# DST800_NMEA2k-CAN_Indicator.net
KiCad netlist of a schematic drawn in Altium Designer
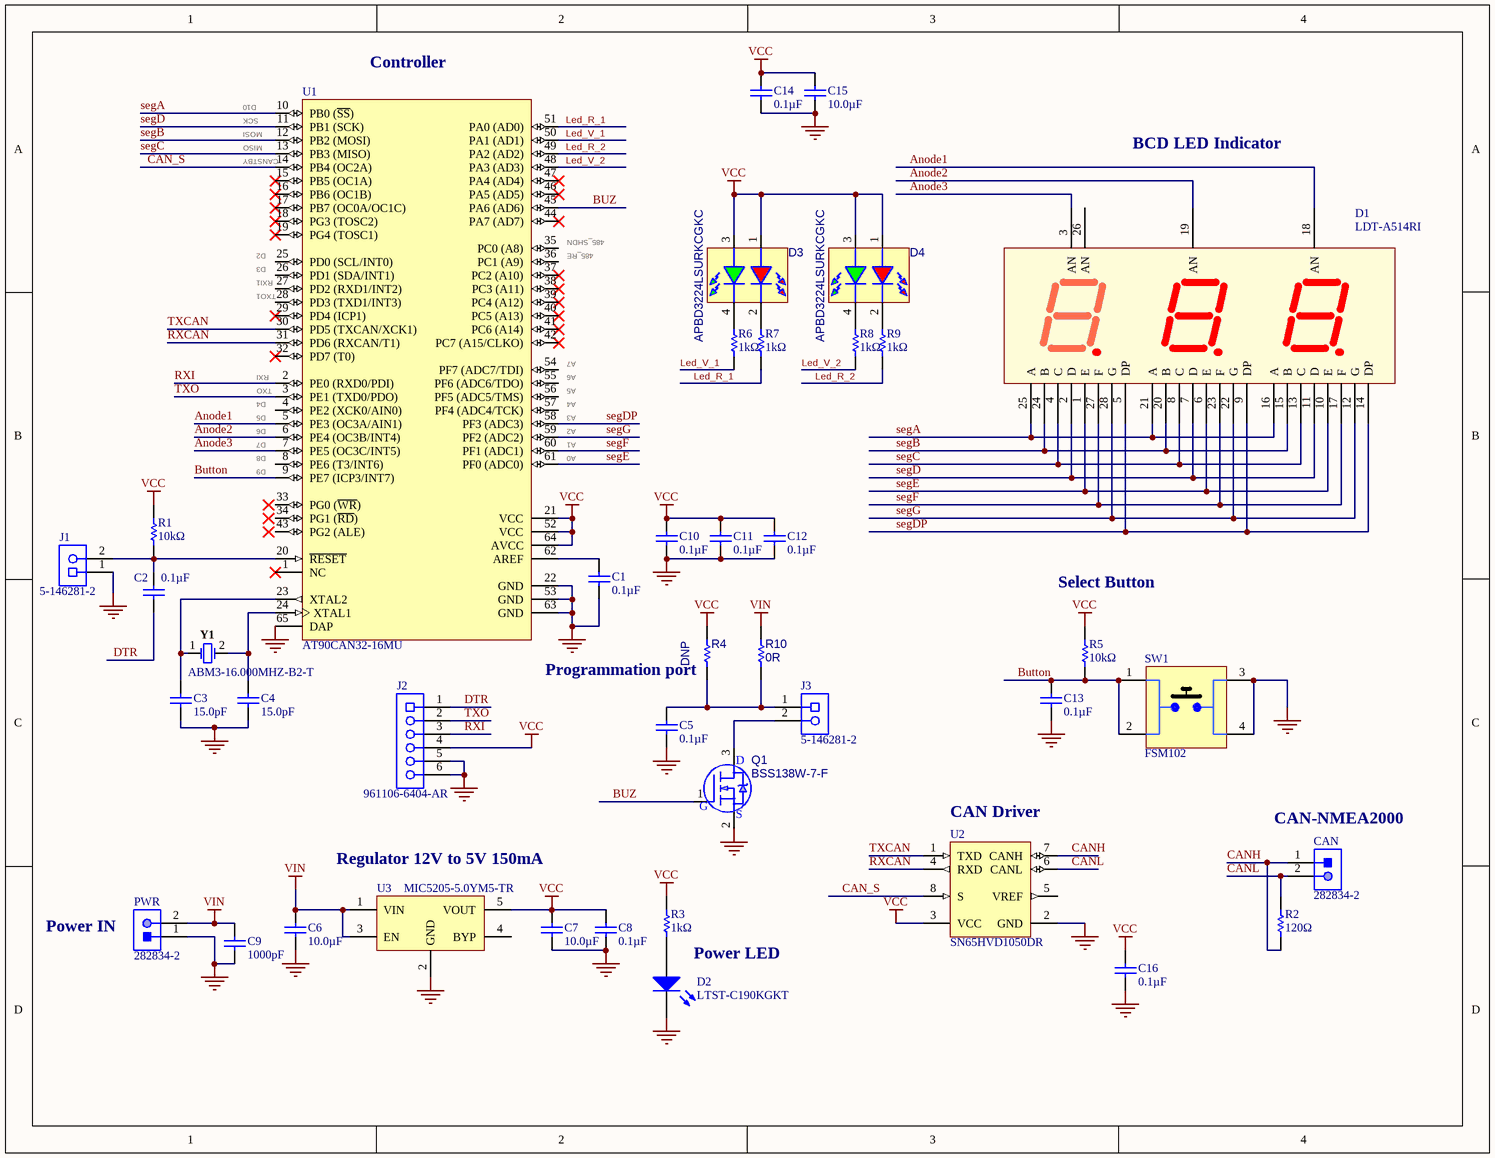
[diagram p0: DST800_NMEA2k-CAN_Indicator.SchDoc]

(export (version "E")
  (design (tool "Eeschema 10.0.6"))
  (components
    (comp (ref "C1")
      (value "0.1µF")
      (footprint "PCB-mhhqftc5ilnrg4qi8ds6-1")
      (description "CAP CER 0.1uF 50V X7R 0603")
      (fields
        (field (name "MANUFACTURER") "Samsung Electro-Mechanics")
        (field (name "MANUFACTURERPARTNUMBER") "CL10B104KB8NNNC")
      )
      (libsource (lib "DST800_NMEA2k-CAN_Indicator") (part "CMP-1af8d38ac64bc53f-5"))
    )
    (comp (ref "C2")
      (value "0.1µF")
      (footprint "PCB-mhhqftc5ilnrg4qi8ds6-1")
      (description "CAP CER 0.1uF 50V X7R 0603")
      (fields
        (field (name "MANUFACTURER") "Samsung Electro-Mechanics")
        (field (name "MANUFACTURERPARTNUMBER") "CL10B104KB8NNNC")
      )
      (libsource (lib "DST800_NMEA2k-CAN_Indicator") (part "CMP-1af8d38ac64bc53f-5"))
    )
    (comp (ref "C3")
      (value "15.0pF")
      (footprint "PCB-69ec8bfnjhyebnpbrrfx-1")
      (description "CAP CER 15pF ±5% 50V C0G/NP0 0603 [1608]")
      (fields
        (field (name "MANUFACTURER") "TDK")
        (field (name "MANUFACTURERPARTNUMBER") "C1608C0G1H150J080AA")
      )
      (libsource (lib "DST800_NMEA2k-CAN_Indicator") (part "CMP-57259fa49f8088e2-2"))
    )
    (comp (ref "C4")
      (value "15.0pF")
      (footprint "PCB-69ec8bfnjhyebnpbrrfx-1")
      (description "CAP CER 15pF ±5% 50V C0G/NP0 0603 [1608]")
      (fields
        (field (name "MANUFACTURER") "TDK")
        (field (name "MANUFACTURERPARTNUMBER") "C1608C0G1H150J080AA")
      )
      (libsource (lib "DST800_NMEA2k-CAN_Indicator") (part "CMP-57259fa49f8088e2-2"))
    )
    (comp (ref "C5")
      (value "0.1µF")
      (footprint "PCB-mhhqftc5ilnrg4qi8ds6-1")
      (description "CAP CER 0.1uF 50V X7R 0603")
      (fields
        (field (name "MANUFACTURER") "Samsung Electro-Mechanics")
        (field (name "MANUFACTURERPARTNUMBER") "CL10B104KB8NNNC")
      )
      (libsource (lib "DST800_NMEA2k-CAN_Indicator") (part "CMP-1af8d38ac64bc53f-5"))
    )
    (comp (ref "C6")
      (value "10.0µF")
      (footprint "PCB-j0jk5xr8qbnaskonccg4-1")
      (description "CAP CER 10uF ±10% 25V X7R 1210")
      (fields
        (field (name "MANUFACTURER") "TDK")
        (field (name "MANUFACTURERPARTNUMBER") "C3225X7R1E106K250AC")
      )
      (libsource (lib "DST800_NMEA2k-CAN_Indicator") (part "CMP-2bdce35de069f41b-1"))
    )
    (comp (ref "C7")
      (value "10.0µF")
      (footprint "PCB-j0jk5xr8qbnaskonccg4-1")
      (description "CAP CER 10uF ±10% 25V X7R 1210")
      (fields
        (field (name "MANUFACTURER") "TDK")
        (field (name "MANUFACTURERPARTNUMBER") "C3225X7R1E106K250AC")
      )
      (libsource (lib "DST800_NMEA2k-CAN_Indicator") (part "CMP-2bdce35de069f41b-1"))
    )
    (comp (ref "C8")
      (value "0.1µF")
      (footprint "PCB-mhhqftc5ilnrg4qi8ds6-1")
      (description "CAP CER 0.1uF 50V X7R 0603")
      (fields
        (field (name "MANUFACTURER") "Samsung Electro-Mechanics")
        (field (name "MANUFACTURERPARTNUMBER") "CL10B104KB8NNNC")
      )
      (libsource (lib "DST800_NMEA2k-CAN_Indicator") (part "CMP-1af8d38ac64bc53f-5"))
    )
    (comp (ref "C9")
      (value "1000pF")
      (footprint "CAPC1608X90X35LL15T15")
      (description "CAP CER 1000pF ±20% 100V X7R 0603")
      (fields (field (name "MANUFACTURERPARTNUMBER") "06031C102MAT2A") (field (name "MANUFACTURER") "AVX"))
      (libsource (lib "DST800_NMEA2k-CAN_Indicator") (part "CMP-126202-2"))
    )
    (comp (ref "C10")
      (value "0.1µF")
      (footprint "PCB-mhhqftc5ilnrg4qi8ds6-1")
      (description "CAP CER 0.1uF 50V X7R 0603")
      (fields
        (field (name "MANUFACTURER") "Samsung Electro-Mechanics")
        (field (name "MANUFACTURERPARTNUMBER") "CL10B104KB8NNNC")
      )
      (libsource (lib "DST800_NMEA2k-CAN_Indicator") (part "CMP-1af8d38ac64bc53f-5"))
    )
    (comp (ref "C11")
      (value "0.1µF")
      (footprint "PCB-mhhqftc5ilnrg4qi8ds6-1")
      (description "CAP CER 0.1uF 50V X7R 0603")
      (fields
        (field (name "MANUFACTURER") "Samsung Electro-Mechanics")
        (field (name "MANUFACTURERPARTNUMBER") "CL10B104KB8NNNC")
      )
      (libsource (lib "DST800_NMEA2k-CAN_Indicator") (part "CMP-1af8d38ac64bc53f-5"))
    )
    (comp (ref "C12")
      (value "0.1µF")
      (footprint "PCB-mhhqftc5ilnrg4qi8ds6-1")
      (description "CAP CER 0.1uF 50V X7R 0603")
      (fields
        (field (name "MANUFACTURER") "Samsung Electro-Mechanics")
        (field (name "MANUFACTURERPARTNUMBER") "CL10B104KB8NNNC")
      )
      (libsource (lib "DST800_NMEA2k-CAN_Indicator") (part "CMP-1af8d38ac64bc53f-5"))
    )
    (comp (ref "C13")
      (value "0.1µF")
      (footprint "PCB-mhhqftc5ilnrg4qi8ds6-1")
      (description "CAP CER 0.1uF 50V X7R 0603")
      (fields
        (field (name "MANUFACTURER") "Samsung Electro-Mechanics")
        (field (name "MANUFACTURERPARTNUMBER") "CL10B104KB8NNNC")
      )
      (libsource (lib "DST800_NMEA2k-CAN_Indicator") (part "CMP-1af8d38ac64bc53f-5"))
    )
    (comp (ref "C14")
      (value "0.1µF")
      (footprint "PCB-mhhqftc5ilnrg4qi8ds6-1")
      (description "CAP CER 0.1uF 50V X7R 0603")
      (fields
        (field (name "MANUFACTURER") "Samsung Electro-Mechanics")
        (field (name "MANUFACTURERPARTNUMBER") "CL10B104KB8NNNC")
      )
      (libsource (lib "DST800_NMEA2k-CAN_Indicator") (part "CMP-1af8d38ac64bc53f-5"))
    )
    (comp (ref "C15")
      (value "10.0µF")
      (footprint "PCB-j0jk5xr8qbnaskonccg4-1")
      (description "CAP CER 10uF ±10% 25V X7R 1210")
      (fields
        (field (name "MANUFACTURER") "TDK")
        (field (name "MANUFACTURERPARTNUMBER") "C3225X7R1E106K250AC")
      )
      (libsource (lib "DST800_NMEA2k-CAN_Indicator") (part "CMP-2bdce35de069f41b-1"))
    )
    (comp (ref "C16")
      (value "0.1µF")
      (footprint "PCB-mhhqftc5ilnrg4qi8ds6-1")
      (description "CAP CER 0.1uF 50V X7R 0603")
      (fields
        (field (name "MANUFACTURER") "Samsung Electro-Mechanics")
        (field (name "MANUFACTURERPARTNUMBER") "CL10B104KB8NNNC")
      )
      (libsource (lib "DST800_NMEA2k-CAN_Indicator") (part "CMP-1af8d38ac64bc53f-5"))
    )
    (comp (ref "CAN")
      (value "282834-2")
      (footprint "PCB-0kdx5sneyudsmu18l6zv-1")
      (description "CONN Terminal Block; 16-30 AWG 0.197 in")
      (fields (field (name "MANUFACTURER") "TE Connectivity"))
      (libsource (lib "DST800_NMEA2k-CAN_Indicator") (part "CMP-369bfdc835bbe95c-32"))
    )
    (comp (ref "D1")
      (value "LDT-A514RI")
      (footprint "LDTA514RI")
      (description "Display 3-digit 7-Seg 0.56 in")
      (fields (field (name "MANUFACTURER") "Lumex"))
      (libsource (lib "DST800_NMEA2k-CAN_Indicator") (part "CMP-6dbba4b18441b27c-1"))
    )
    (comp (ref "D2")
      (value "LTST-C190KGKT")
      (footprint "PCB-eapfwhp0rnksgujf96h3-1")
      (description "LED 0603 green")
      (fields (field (name "MANUFACTURER") "Lite-On"))
      (libsource (lib "DST800_NMEA2k-CAN_Indicator") (part "CMP-e1642866a00b3ea3-3"))
    )
    (comp (ref "D3")
      (value "APBD3224LSURKCGKC")
      (footprint "DS_LED_3224")
      (description "LED Red and Yellow-Green")
      (fields (field (name "MANUFACTURER") "Kingbright"))
      (libsource (lib "NewLib_KCO") (part "D_LED_RED_Y-GREEN_3224"))
    )
    (comp (ref "D4")
      (value "APBD3224LSURKCGKC")
      (footprint "DS_LED_3224")
      (description "LED Red and Yellow-Green")
      (fields (field (name "MANUFACTURER") "Kingbright"))
      (libsource (lib "NewLib_KCO") (part "D_LED_RED_Y-GREEN_3224"))
    )
    (comp (ref "J1")
      (value "5-146281-2")
      (footprint "PCB-angfy19quc8nc8nc7d0m-1")
      (description "CONN HEADER VERT 2POS Single 0.1in pitch")
      (fields (field (name "MANUFACTURER") "TE Connectivity"))
      (libsource (lib "") (part "CMP-39c9f206a0b6e60e-14_1"))
    )
    (comp (ref "J2")
      (value "961106-6404-AR")
      (footprint "PCB-660833-1")
      (description "CONN HEADER VERT 6POS Single 0.1in pitch")
      (fields (field (name "MANUFACTURER") "3M"))
      (libsource (lib "DST800_NMEA2k-CAN_Indicator") (part "CMP-660833-2"))
    )
    (comp (ref "J3")
      (value "5-146281-2")
      (footprint "PCB-angfy19quc8nc8nc7d0m-1")
      (description "CONN HEADER VERT 2POS Single 0.1in pitch")
      (fields (field (name "MANUFACTURER") "TE Connectivity"))
      (libsource (lib "DST800_NMEA2k-CAN_Indicator") (part "CMP-39c9f206a0b6e60e-14"))
    )
    (comp (ref "PWR")
      (value "282834-2")
      (footprint "PCB-0kdx5sneyudsmu18l6zv-1")
      (description "CONN Terminal Block; 16-30 AWG 0.197 in")
      (fields (field (name "MANUFACTURER") "TE Connectivity"))
      (libsource (lib "") (part "CMP-369bfdc835bbe95c-32_1"))
    )
    (comp (ref "Q1")
      (value "BSS138W-7-F")
      (footprint "SOT323-3N")
      (description "NMOS 200mA")
      (fields (field (name "MANUFACTURER") "Diodes inc"))
      (libsource (lib "SAP") (part "Q_BSS138W"))
    )
    (comp (ref "R1")
      (value "10kΩ")
      (footprint "RESC1608X55X30NL15T15")
      (description "RES 10K 1% 0.1W 0603")
      (fields
        (field (name "MANUFACTURERPARTNUMBER") "CRG0603F10K")
        (field (name "MANUFACTURER") "TE Connectivity")
      )
      (libsource (lib "DST800_NMEA2k-CAN_Indicator") (part "CMP-584891b72cc4878f-2"))
    )
    (comp (ref "R2")
      (value "120Ω")
      (footprint "RESC3216X60X45LL10T20")
      (description "RES Thick Film 120ohm 5% 1/4W 1206")
      (fields
        (field (name "MANUFACTURERPARTNUMBER") "CRCW1206120RJNEA")
        (field (name "MANUFACTURER") "Vishay")
      )
      (libsource (lib "DST800_NMEA2k-CAN_Indicator") (part "CMP-1858100-4"))
    )
    (comp (ref "R3")
      (value "1kΩ")
      (footprint "RESC1608X55X30NL20T20")
      (description "RES Metal Film 1Kohm 0.1%  0603")
      (fields
        (field (name "MANUFACTURERPARTNUMBER") "ERA-3AEB102V")
        (field (name "MANUFACTURER") "Panasonic")
      )
      (libsource (lib "DST800_NMEA2k-CAN_Indicator") (part "CMP-3717598-2"))
    )
    (comp (ref "R4")
      (value "DNP")
      (footprint "R_1005[0402]")
      (description "Chip Resistor")
      (fields (field (name "MANUFACTURER") "Vishay-Dale") (field (name "TOLERANCE") "jumper"))
      (libsource (lib "RLC_SAP") (part "R_0R_0,0625W_0402"))
    )
    (comp (ref "R5")
      (value "10kΩ")
      (footprint "RESC1608X55X30NL15T15")
      (description "RES 10K 1% 0.1W 0603")
      (fields
        (field (name "MANUFACTURERPARTNUMBER") "CRG0603F10K")
        (field (name "MANUFACTURER") "TE Connectivity")
      )
      (libsource (lib "DST800_NMEA2k-CAN_Indicator") (part "CMP-584891b72cc4878f-2"))
    )
    (comp (ref "R6")
      (value "1kΩ")
      (footprint "RESC1608X55X30NL20T20")
      (description "RES Metal Film 1Kohm 0.1%  0603")
      (fields
        (field (name "MANUFACTURERPARTNUMBER") "ERA-3AEB102V")
        (field (name "MANUFACTURER") "Panasonic")
      )
      (libsource (lib "DST800_NMEA2k-CAN_Indicator") (part "CMP-3717598-2"))
    )
    (comp (ref "R7")
      (value "1kΩ")
      (footprint "RESC1608X55X30NL20T20")
      (description "RES Metal Film 1Kohm 0.1%  0603")
      (fields
        (field (name "MANUFACTURERPARTNUMBER") "ERA-3AEB102V")
        (field (name "MANUFACTURER") "Panasonic")
      )
      (libsource (lib "DST800_NMEA2k-CAN_Indicator") (part "CMP-3717598-2"))
    )
    (comp (ref "R8")
      (value "1kΩ")
      (footprint "RESC1608X55X30NL20T20")
      (description "RES Metal Film 1Kohm 0.1%  0603")
      (fields
        (field (name "MANUFACTURERPARTNUMBER") "ERA-3AEB102V")
        (field (name "MANUFACTURER") "Panasonic")
      )
      (libsource (lib "DST800_NMEA2k-CAN_Indicator") (part "CMP-3717598-2"))
    )
    (comp (ref "R9")
      (value "1kΩ")
      (footprint "RESC1608X55X30NL20T20")
      (description "RES Metal Film 1Kohm 0.1%  0603")
      (fields
        (field (name "MANUFACTURERPARTNUMBER") "ERA-3AEB102V")
        (field (name "MANUFACTURER") "Panasonic")
      )
      (libsource (lib "DST800_NMEA2k-CAN_Indicator") (part "CMP-3717598-2"))
    )
    (comp (ref "R10")
      (value "0R")
      (footprint "R_1005[0402]")
      (description "Chip Resistor")
      (fields (field (name "MANUFACTURER") "Vishay-Dale") (field (name "TOLERANCE") "jumper"))
      (libsource (lib "RLC_SAP") (part "R_0R_0,0625W_0402"))
    )
    (comp (ref "SW1")
      (value "FSM102")
      (footprint "PCB-8ps4wla3pj92cxv2yuvu-1")
      (description "PUSHBUTTON Momentary Tactile SPST Thru-Hole")
      (fields (field (name "MANUFACTURER") "TE Connectivity"))
      (libsource (lib "DST800_NMEA2k-CAN_Indicator") (part "CMP-43e488b0e8c29c23-11"))
    )
    (comp (ref "U1")
      (value "AT90CAN32-16MU")
      (footprint "Z64-1_M")
      (libsource (lib "Altium Content Vault") (part "MC-8B-AT90CAN32-SQ65"))
    )
    (comp (ref "U2")
      (value "SN65HVD1050DR")
      (footprint "D0008A_L")
      (fields (field (name "MANUFACTURER") "Texas Instruments"))
      (libsource (lib "Altium Content Vault") (part "TI-SN65HVD1050-SOIC_D-8"))
    )
    (comp (ref "U3")
      (value "MIC5205-5.0YM5-TR")
      (footprint "SOT-23-5_N")
      (description "IC Regulator LDO 5 V Fixed Output 150 mA SOT-23-5")
      (fields (field (name "MANUFACTURER") "Microchip"))
      (libsource (lib "DST800_NMEA2k-CAN_Indicator") (part "CMP-6255a8a416e5bd92-5"))
    )
    (comp (ref "Y1")
      (value "ABM3-16.000MHZ-B2-T")
      (footprint "ABRA-ABM3_V")
      (description "Ceramic Crystal, 16 MHz, 2-Pin SMD")
      (fields (field (name "MANUFACTURER") "ABRACON"))
      (libsource (lib "DST800_NMEA2k-CAN_Indicator") (part "CMP-2000-05729-1"))
    )
  )
  (nets
    (net (code "1") (name "/Anode1") (class "Default")
      (node (ref "D1") (pin "18") (pinfunction "AN_18") (pintype "passive"))
      (node (ref "U1") (pin "5") (pinfunction "PE3_(OC3A/AIN1)_5") (pintype "bidirectional"))
    )
    (net (code "2") (name "/Anode2") (class "Default")
      (node (ref "D1") (pin "19") (pinfunction "AN_19") (pintype "passive"))
      (node (ref "U1") (pin "6") (pinfunction "PE4_(OC3B/INT4)_6") (pintype "bidirectional"))
    )
    (net (code "3") (name "/Anode3") (class "Default")
      (node (ref "D1") (pin "3") (pinfunction "AN_3") (pintype "passive"))
      (node (ref "U1") (pin "7") (pinfunction "PE5_(OC3C/INT5)_7") (pintype "bidirectional"))
    )
    (net (code "4") (name "/BUZ") (class "Default")
      (node (ref "Q1") (pin "1") (pinfunction "G_1") (pintype "passive"))
      (node (ref "U1") (pin "45") (pinfunction "PA6_(AD6)_45") (pintype "bidirectional"))
    )
    (net (code "5") (name "/Button") (class "Default")
      (node (ref "C13") (pin "2") (pinfunction "2_2") (pintype "passive"))
      (node (ref "R5") (pin "1") (pinfunction "1_1") (pintype "passive"))
      (node (ref "SW1") (pin "1") (pinfunction "1_1") (pintype "passive"))
      (node (ref "SW1") (pin "2") (pinfunction "2_2") (pintype "passive"))
      (node (ref "U1") (pin "9") (pinfunction "PE7_(ICP3/INT7)_9") (pintype "bidirectional"))
    )
    (net (code "6") (name "/CANH") (class "Default")
      (node (ref "CAN") (pin "1") (pinfunction "1_1") (pintype "passive"))
      (node (ref "R2") (pin "1") (pinfunction "1_1") (pintype "passive"))
      (node (ref "U2") (pin "7") (pinfunction "CANH_7") (pintype "bidirectional"))
    )
    (net (code "7") (name "/CANL") (class "Default")
      (node (ref "CAN") (pin "2") (pinfunction "2_2") (pintype "passive"))
      (node (ref "R2") (pin "2") (pinfunction "2_2") (pintype "passive"))
      (node (ref "U2") (pin "6") (pinfunction "CANL_6") (pintype "bidirectional"))
    )
    (net (code "8") (name "/CAN_S") (class "Default")
      (node (ref "U1") (pin "14") (pinfunction "PB4_(OC2A)_14") (pintype "bidirectional"))
      (node (ref "U2") (pin "8") (pinfunction "S_8") (pintype "input"))
    )
    (net (code "9") (name "/DTR") (class "Default")
      (node (ref "C2") (pin "1") (pinfunction "1_1") (pintype "passive"))
      (node (ref "J2") (pin "1") (pinfunction "1_1") (pintype "passive"))
    )
    (net (code "10") (name "/Led_R_1") (class "Default")
      (node (ref "R7") (pin "2") (pinfunction "2_2") (pintype "passive"))
      (node (ref "U1") (pin "51") (pinfunction "PA0_(AD0)_51") (pintype "bidirectional"))
    )
    (net (code "11") (name "/Led_R_2") (class "Default")
      (node (ref "R9") (pin "2") (pinfunction "2_2") (pintype "passive"))
      (node (ref "U1") (pin "49") (pinfunction "PA2_(AD2)_49") (pintype "bidirectional"))
    )
    (net (code "12") (name "/Led_V_1") (class "Default")
      (node (ref "R6") (pin "2") (pinfunction "2_2") (pintype "passive"))
      (node (ref "U1") (pin "50") (pinfunction "PA1_(AD1)_50") (pintype "bidirectional"))
    )
    (net (code "13") (name "/Led_V_2") (class "Default")
      (node (ref "R8") (pin "2") (pinfunction "2_2") (pintype "passive"))
      (node (ref "U1") (pin "48") (pinfunction "PA3_(AD3)_48") (pintype "bidirectional"))
    )
    (net (code "14") (name "/RXCAN") (class "Default")
      (node (ref "U1") (pin "31") (pinfunction "PD6_(RXCAN/T1)_31") (pintype "bidirectional"))
      (node (ref "U2") (pin "4") (pinfunction "RXD_4") (pintype "output"))
    )
    (net (code "15") (name "/RXI") (class "Default")
      (node (ref "J2") (pin "3") (pinfunction "3_3") (pintype "passive"))
      (node (ref "U1") (pin "2") (pinfunction "PE0_(RXD0/PDI)_2") (pintype "bidirectional"))
    )
    (net (code "16") (name "/TXCAN") (class "Default")
      (node (ref "U1") (pin "30") (pinfunction "PD5_(TXCAN/XCK1)_30") (pintype "bidirectional"))
      (node (ref "U2") (pin "1") (pinfunction "TXD_1") (pintype "input"))
    )
    (net (code "17") (name "/TXO") (class "Default")
      (node (ref "J2") (pin "2") (pinfunction "2_2") (pintype "passive"))
      (node (ref "U1") (pin "3") (pinfunction "PE1_(TXD0/PDO)_3") (pintype "bidirectional"))
    )
    (net (code "18") (name "/segA") (class "Default")
      (node (ref "D1") (pin "16") (pinfunction "A_16") (pintype "passive"))
      (node (ref "D1") (pin "21") (pinfunction "A_21") (pintype "passive"))
      (node (ref "D1") (pin "25") (pinfunction "A_25") (pintype "passive"))
      (node (ref "U1") (pin "10") (pinfunction "PB0_(~{SS})_10") (pintype "bidirectional"))
    )
    (net (code "19") (name "/segB") (class "Default")
      (node (ref "D1") (pin "15") (pinfunction "B_15") (pintype "passive"))
      (node (ref "D1") (pin "20") (pinfunction "B_20") (pintype "passive"))
      (node (ref "D1") (pin "24") (pinfunction "B_24") (pintype "passive"))
      (node (ref "U1") (pin "12") (pinfunction "PB2_(MOSI)_12") (pintype "bidirectional"))
    )
    (net (code "20") (name "/segC") (class "Default")
      (node (ref "D1") (pin "13") (pinfunction "C_13") (pintype "passive"))
      (node (ref "D1") (pin "4") (pinfunction "C_4") (pintype "passive"))
      (node (ref "D1") (pin "8") (pinfunction "C_8") (pintype "passive"))
      (node (ref "U1") (pin "13") (pinfunction "PB3_(MISO)_13") (pintype "bidirectional"))
    )
    (net (code "21") (name "/segD") (class "Default")
      (node (ref "D1") (pin "11") (pinfunction "D_11") (pintype "passive"))
      (node (ref "D1") (pin "2") (pinfunction "D_2") (pintype "passive"))
      (node (ref "D1") (pin "7") (pinfunction "D_7") (pintype "passive"))
      (node (ref "U1") (pin "11") (pinfunction "PB1_(SCK)_11") (pintype "bidirectional"))
    )
    (net (code "22") (name "/segDP") (class "Default")
      (node (ref "D1") (pin "14") (pinfunction "DP_14") (pintype "passive"))
      (node (ref "D1") (pin "5") (pinfunction "DP_5") (pintype "passive"))
      (node (ref "D1") (pin "9") (pinfunction "DP_9") (pintype "passive"))
      (node (ref "U1") (pin "58") (pinfunction "PF3_(ADC3)_58") (pintype "bidirectional"))
    )
    (net (code "23") (name "/segE") (class "Default")
      (node (ref "D1") (pin "1") (pinfunction "E_1") (pintype "passive"))
      (node (ref "D1") (pin "10") (pinfunction "E_10") (pintype "passive"))
      (node (ref "D1") (pin "6") (pinfunction "E_6") (pintype "passive"))
      (node (ref "U1") (pin "61") (pinfunction "PF0_(ADC0)_61") (pintype "bidirectional"))
    )
    (net (code "24") (name "/segF") (class "Default")
      (node (ref "D1") (pin "17") (pinfunction "F_17") (pintype "passive"))
      (node (ref "D1") (pin "23") (pinfunction "F_23") (pintype "passive"))
      (node (ref "D1") (pin "27") (pinfunction "F_27") (pintype "passive"))
      (node (ref "U1") (pin "60") (pinfunction "PF1_(ADC1)_60") (pintype "bidirectional"))
    )
    (net (code "25") (name "/segG") (class "Default")
      (node (ref "D1") (pin "12") (pinfunction "G_12") (pintype "passive"))
      (node (ref "D1") (pin "22") (pinfunction "G_22") (pintype "passive"))
      (node (ref "D1") (pin "28") (pinfunction "G_28") (pintype "passive"))
      (node (ref "U1") (pin "59") (pinfunction "PF2_(ADC2)_59") (pintype "bidirectional"))
    )
    (net (code "26") (name "GND") (class "Default")
      (node (ref "C1") (pin "1") (pinfunction "1_1") (pintype "passive"))
      (node (ref "C10") (pin "1") (pinfunction "1_1") (pintype "passive"))
      (node (ref "C11") (pin "1") (pinfunction "1_1") (pintype "passive"))
      (node (ref "C12") (pin "1") (pinfunction "1_1") (pintype "passive"))
      (node (ref "C13") (pin "1") (pinfunction "1_1") (pintype "passive"))
      (node (ref "C14") (pin "1") (pinfunction "1_1") (pintype "passive"))
      (node (ref "C15") (pin "1") (pinfunction "1_1") (pintype "passive"))
      (node (ref "C16") (pin "1") (pinfunction "1_1") (pintype "passive"))
      (node (ref "C3") (pin "1") (pinfunction "1_1") (pintype "passive"))
      (node (ref "C4") (pin "1") (pinfunction "1_1") (pintype "passive"))
      (node (ref "C5") (pin "1") (pinfunction "1_1") (pintype "passive"))
      (node (ref "C6") (pin "1") (pinfunction "1_1") (pintype "passive"))
      (node (ref "C7") (pin "1") (pinfunction "1_1") (pintype "passive"))
      (node (ref "C8") (pin "1") (pinfunction "1_1") (pintype "passive"))
      (node (ref "C9") (pin "1") (pinfunction "1_1") (pintype "passive"))
      (node (ref "D2") (pin "2") (pinfunction "K_2") (pintype "passive"))
      (node (ref "J1") (pin "1") (pinfunction "1_1") (pintype "passive"))
      (node (ref "J2") (pin "5") (pinfunction "5_5") (pintype "passive"))
      (node (ref "J2") (pin "6") (pinfunction "6_6") (pintype "passive"))
      (node (ref "PWR") (pin "1") (pinfunction "1_1") (pintype "passive"))
      (node (ref "Q1") (pin "2") (pinfunction "S_2") (pintype "passive"))
      (node (ref "SW1") (pin "3") (pinfunction "3_3") (pintype "passive"))
      (node (ref "SW1") (pin "4") (pinfunction "4_4") (pintype "passive"))
      (node (ref "U1") (pin "22") (pinfunction "GND_22") (pintype "power_in"))
      (node (ref "U1") (pin "53") (pinfunction "GND_53") (pintype "power_in"))
      (node (ref "U1") (pin "63") (pinfunction "GND_63") (pintype "power_in"))
      (node (ref "U1") (pin "65") (pinfunction "DAP_65") (pintype "power_in"))
      (node (ref "U2") (pin "2") (pinfunction "GND_2") (pintype "power_in"))
      (node (ref "U3") (pin "2") (pinfunction "GND_2") (pintype "passive"))
    )
    (net (code "27") (name "Net-(C5-Pad2)") (class "Default")
      (node (ref "C5") (pin "2") (pinfunction "2_2") (pintype "passive"))
      (node (ref "J3") (pin "1") (pinfunction "1_1") (pintype "passive"))
      (node (ref "R10") (pin "1") (pinfunction "1_1") (pintype "passive"))
      (node (ref "R4") (pin "1") (pinfunction "1_1") (pintype "passive"))
    )
    (net (code "28") (name "Net-(D2-A)") (class "Default")
      (node (ref "D2") (pin "1") (pinfunction "A_1") (pintype "passive"))
      (node (ref "R3") (pin "1") (pinfunction "1_1") (pintype "passive"))
    )
    (net (code "29") (name "Net-(D3-Pad2)") (class "Default")
      (node (ref "D3") (pin "2") (pinfunction "2_2") (pintype "passive"))
      (node (ref "R7") (pin "1") (pinfunction "1_1") (pintype "passive"))
    )
    (net (code "30") (name "Net-(D3-Pad4)") (class "Default")
      (node (ref "D3") (pin "4") (pinfunction "4_4") (pintype "passive"))
      (node (ref "R6") (pin "1") (pinfunction "1_1") (pintype "passive"))
    )
    (net (code "31") (name "Net-(D4-Pad2)") (class "Default")
      (node (ref "D4") (pin "2") (pinfunction "2_2") (pintype "passive"))
      (node (ref "R9") (pin "1") (pinfunction "1_1") (pintype "passive"))
    )
    (net (code "32") (name "Net-(D4-Pad4)") (class "Default")
      (node (ref "D4") (pin "4") (pinfunction "4_4") (pintype "passive"))
      (node (ref "R8") (pin "1") (pinfunction "1_1") (pintype "passive"))
    )
    (net (code "33") (name "Net-(Q1-D)") (class "Default")
      (node (ref "J3") (pin "2") (pinfunction "2_2") (pintype "passive"))
      (node (ref "Q1") (pin "3") (pinfunction "D_3") (pintype "passive"))
    )
    (net (code "34") (name "Net-(U1-AREF)") (class "Default")
      (node (ref "C1") (pin "2") (pinfunction "2_2") (pintype "passive"))
      (node (ref "U1") (pin "62") (pinfunction "AREF_62") (pintype "power_in"))
    )
    (net (code "35") (name "Net-(U1-XTAL1)") (class "Default")
      (node (ref "C4") (pin "2") (pinfunction "2_2") (pintype "passive"))
      (node (ref "U1") (pin "24") (pinfunction "XTAL1_24") (pintype "input"))
      (node (ref "Y1") (pin "2") (pinfunction "2_2") (pintype "passive"))
    )
    (net (code "36") (name "Net-(U1-XTAL2)") (class "Default")
      (node (ref "C3") (pin "2") (pinfunction "2_2") (pintype "passive"))
      (node (ref "U1") (pin "23") (pinfunction "XTAL2_23") (pintype "output"))
      (node (ref "Y1") (pin "1") (pinfunction "1_1") (pintype "passive"))
    )
    (net (code "37") (name "Net-(U1-~{RESET})") (class "Default")
      (node (ref "C2") (pin "2") (pinfunction "2_2") (pintype "passive"))
      (node (ref "J1") (pin "2") (pinfunction "2_2") (pintype "passive"))
      (node (ref "R1") (pin "1") (pinfunction "1_1") (pintype "passive"))
      (node (ref "U1") (pin "20") (pinfunction "~{RESET}_20") (pintype "input"))
    )
    (net (code "38") (name "VCC") (class "Default")
      (node (ref "C10") (pin "2") (pinfunction "2_2") (pintype "passive"))
      (node (ref "C11") (pin "2") (pinfunction "2_2") (pintype "passive"))
      (node (ref "C12") (pin "2") (pinfunction "2_2") (pintype "passive"))
      (node (ref "C14") (pin "2") (pinfunction "2_2") (pintype "passive"))
      (node (ref "C15") (pin "2") (pinfunction "2_2") (pintype "passive"))
      (node (ref "C16") (pin "2") (pinfunction "2_2") (pintype "passive"))
      (node (ref "C7") (pin "2") (pinfunction "2_2") (pintype "passive"))
      (node (ref "C8") (pin "2") (pinfunction "2_2") (pintype "passive"))
      (node (ref "D3") (pin "1") (pinfunction "1_1") (pintype "passive"))
      (node (ref "D3") (pin "3") (pinfunction "3_3") (pintype "passive"))
      (node (ref "D4") (pin "1") (pinfunction "1_1") (pintype "passive"))
      (node (ref "D4") (pin "3") (pinfunction "3_3") (pintype "passive"))
      (node (ref "J2") (pin "4") (pinfunction "4_4") (pintype "passive"))
      (node (ref "R1") (pin "2") (pinfunction "2_2") (pintype "passive"))
      (node (ref "R3") (pin "2") (pinfunction "2_2") (pintype "passive"))
      (node (ref "R4") (pin "2") (pinfunction "2_2") (pintype "passive"))
      (node (ref "R5") (pin "2") (pinfunction "2_2") (pintype "passive"))
      (node (ref "U1") (pin "21") (pinfunction "VCC_21") (pintype "power_in"))
      (node (ref "U1") (pin "52") (pinfunction "VCC_52") (pintype "power_in"))
      (node (ref "U1") (pin "64") (pinfunction "AVCC_64") (pintype "power_in"))
      (node (ref "U2") (pin "3") (pinfunction "VCC_3") (pintype "power_in"))
      (node (ref "U3") (pin "5") (pinfunction "VOUT_5") (pintype "passive"))
    )
    (net (code "39") (name "VIN") (class "Default")
      (node (ref "C6") (pin "2") (pinfunction "2_2") (pintype "passive"))
      (node (ref "C9") (pin "2") (pinfunction "2_2") (pintype "passive"))
      (node (ref "PWR") (pin "2") (pinfunction "2_2") (pintype "passive"))
      (node (ref "R10") (pin "2") (pinfunction "2_2") (pintype "passive"))
      (node (ref "U3") (pin "1") (pinfunction "VIN_1") (pintype "passive"))
      (node (ref "U3") (pin "3") (pinfunction "EN_3") (pintype "passive"))
    )
    (net (code "40") (name "unconnected-(D1-AN-Pad26)") (class "Default")
      (node (ref "D1") (pin "26") (pinfunction "AN_26") (pintype "passive"))
    )
    (net (code "41") (name "unconnected-(U1-NC-Pad1)") (class "Default")
      (node (ref "U1") (pin "1") (pinfunction "NC_1") (pintype "passive+no_connect"))
    )
    (net (code "42") (name "unconnected-(U1-PA4_(AD4)-Pad47)") (class "Default")
      (node (ref "U1") (pin "47") (pinfunction "PA4_(AD4)_47") (pintype "bidirectional+no_connect"))
    )
    (net (code "43") (name "unconnected-(U1-PA5_(AD5)-Pad46)") (class "Default")
      (node (ref "U1") (pin "46") (pinfunction "PA5_(AD5)_46") (pintype "bidirectional+no_connect"))
    )
    (net (code "44") (name "unconnected-(U1-PA7_(AD7)-Pad44)") (class "Default")
      (node (ref "U1") (pin "44") (pinfunction "PA7_(AD7)_44") (pintype "bidirectional+no_connect"))
    )
    (net (code "45") (name "unconnected-(U1-PB5_(OC1A)-Pad15)") (class "Default")
      (node (ref "U1") (pin "15") (pinfunction "PB5_(OC1A)_15") (pintype "bidirectional+no_connect"))
    )
    (net (code "46") (name "unconnected-(U1-PB6_(OC1B)-Pad16)") (class "Default")
      (node (ref "U1") (pin "16") (pinfunction "PB6_(OC1B)_16") (pintype "bidirectional+no_connect"))
    )
    (net (code "47") (name "unconnected-(U1-PB7_(OC0A{slash}OC1C)-Pad17)") (class "Default")
      (node (ref "U1") (pin "17") (pinfunction "PB7_(OC0A/OC1C)_17") (pintype "bidirectional+no_connect"))
    )
    (net (code "48") (name "unconnected-(U1-PC0_(A8)-Pad35)") (class "Default")
      (node (ref "U1") (pin "35") (pinfunction "PC0_(A8)_35") (pintype "bidirectional"))
    )
    (net (code "49") (name "unconnected-(U1-PC1_(A9)-Pad36)") (class "Default")
      (node (ref "U1") (pin "36") (pinfunction "PC1_(A9)_36") (pintype "bidirectional"))
    )
    (net (code "50") (name "unconnected-(U1-PC2_(A10)-Pad37)") (class "Default")
      (node (ref "U1") (pin "37") (pinfunction "PC2_(A10)_37") (pintype "bidirectional+no_connect"))
    )
    (net (code "51") (name "unconnected-(U1-PC3_(A11)-Pad38)") (class "Default")
      (node (ref "U1") (pin "38") (pinfunction "PC3_(A11)_38") (pintype "bidirectional+no_connect"))
    )
    (net (code "52") (name "unconnected-(U1-PC4_(A12)-Pad39)") (class "Default")
      (node (ref "U1") (pin "39") (pinfunction "PC4_(A12)_39") (pintype "bidirectional+no_connect"))
    )
    (net (code "53") (name "unconnected-(U1-PC5_(A13)-Pad40)") (class "Default")
      (node (ref "U1") (pin "40") (pinfunction "PC5_(A13)_40") (pintype "bidirectional+no_connect"))
    )
    (net (code "54") (name "unconnected-(U1-PC6_(A14)-Pad41)") (class "Default")
      (node (ref "U1") (pin "41") (pinfunction "PC6_(A14)_41") (pintype "bidirectional+no_connect"))
    )
    (net (code "55") (name "unconnected-(U1-PC7_(A15{slash}CLKO)-Pad42)") (class "Default")
      (node (ref "U1") (pin "42") (pinfunction "PC7_(A15/CLKO)_42") (pintype "bidirectional+no_connect"))
    )
    (net (code "56") (name "unconnected-(U1-PD0_(SCL{slash}INT0)-Pad25)") (class "Default")
      (node (ref "U1") (pin "25") (pinfunction "PD0_(SCL/INT0)_25") (pintype "bidirectional"))
    )
    (net (code "57") (name "unconnected-(U1-PD1_(SDA{slash}INT1)-Pad26)") (class "Default")
      (node (ref "U1") (pin "26") (pinfunction "PD1_(SDA/INT1)_26") (pintype "bidirectional"))
    )
    (net (code "58") (name "unconnected-(U1-PD2_(RXD1{slash}INT2)-Pad27)") (class "Default")
      (node (ref "U1") (pin "27") (pinfunction "PD2_(RXD1/INT2)_27") (pintype "bidirectional"))
    )
    (net (code "59") (name "unconnected-(U1-PD3_(TXD1{slash}INT3)-Pad28)") (class "Default")
      (node (ref "U1") (pin "28") (pinfunction "PD3_(TXD1/INT3)_28") (pintype "bidirectional"))
    )
    (net (code "60") (name "unconnected-(U1-PD4_(ICP1)-Pad29)") (class "Default")
      (node (ref "U1") (pin "29") (pinfunction "PD4_(ICP1)_29") (pintype "bidirectional+no_connect"))
    )
    (net (code "61") (name "unconnected-(U1-PD7_(T0)-Pad32)") (class "Default")
      (node (ref "U1") (pin "32") (pinfunction "PD7_(T0)_32") (pintype "bidirectional+no_connect"))
    )
    (net (code "62") (name "unconnected-(U1-PE2_(XCK0{slash}AIN0)-Pad4)") (class "Default")
      (node (ref "U1") (pin "4") (pinfunction "PE2_(XCK0/AIN0)_4") (pintype "bidirectional"))
    )
    (net (code "63") (name "unconnected-(U1-PE6_(T3{slash}INT6)-Pad8)") (class "Default")
      (node (ref "U1") (pin "8") (pinfunction "PE6_(T3/INT6)_8") (pintype "bidirectional"))
    )
    (net (code "64") (name "unconnected-(U1-PF4_(ADC4{slash}TCK)-Pad57)") (class "Default")
      (node (ref "U1") (pin "57") (pinfunction "PF4_(ADC4/TCK)_57") (pintype "bidirectional"))
    )
    (net (code "65") (name "unconnected-(U1-PF5_(ADC5{slash}TMS)-Pad56)") (class "Default")
      (node (ref "U1") (pin "56") (pinfunction "PF5_(ADC5/TMS)_56") (pintype "bidirectional"))
    )
    (net (code "66") (name "unconnected-(U1-PF6_(ADC6{slash}TDO)-Pad55)") (class "Default")
      (node (ref "U1") (pin "55") (pinfunction "PF6_(ADC6/TDO)_55") (pintype "bidirectional"))
    )
    (net (code "67") (name "unconnected-(U1-PF7_(ADC7{slash}TDI)-Pad54)") (class "Default")
      (node (ref "U1") (pin "54") (pinfunction "PF7_(ADC7/TDI)_54") (pintype "bidirectional"))
    )
    (net (code "68") (name "unconnected-(U1-PG0_(~{WR})-Pad33)") (class "Default")
      (node (ref "U1") (pin "33") (pinfunction "PG0_(~{WR})_33") (pintype "bidirectional"))
    )
    (net (code "69") (name "unconnected-(U1-PG1_(~{RD})-Pad34)") (class "Default")
      (node (ref "U1") (pin "34") (pinfunction "PG1_(~{RD})_34") (pintype "bidirectional"))
    )
    (net (code "70") (name "unconnected-(U1-PG2_(ALE)-Pad43)") (class "Default")
      (node (ref "U1") (pin "43") (pinfunction "PG2_(ALE)_43") (pintype "bidirectional"))
    )
    (net (code "71") (name "unconnected-(U1-PG3_(TOSC2)-Pad18)") (class "Default")
      (node (ref "U1") (pin "18") (pinfunction "PG3_(TOSC2)_18") (pintype "bidirectional+no_connect"))
    )
    (net (code "72") (name "unconnected-(U1-PG4_(TOSC1)-Pad19)") (class "Default")
      (node (ref "U1") (pin "19") (pinfunction "PG4_(TOSC1)_19") (pintype "bidirectional+no_connect"))
    )
    (net (code "73") (name "unconnected-(U2-VREF-Pad5)") (class "Default")
      (node (ref "U2") (pin "5") (pinfunction "VREF_5") (pintype "output"))
    )
    (net (code "74") (name "unconnected-(U3-BYP-Pad4)") (class "Default")
      (node (ref "U3") (pin "4") (pinfunction "BYP_4") (pintype "passive"))
    )
  )
)
